# StepDrv.net
KiCad netlist of a schematic drawn in EAGLE
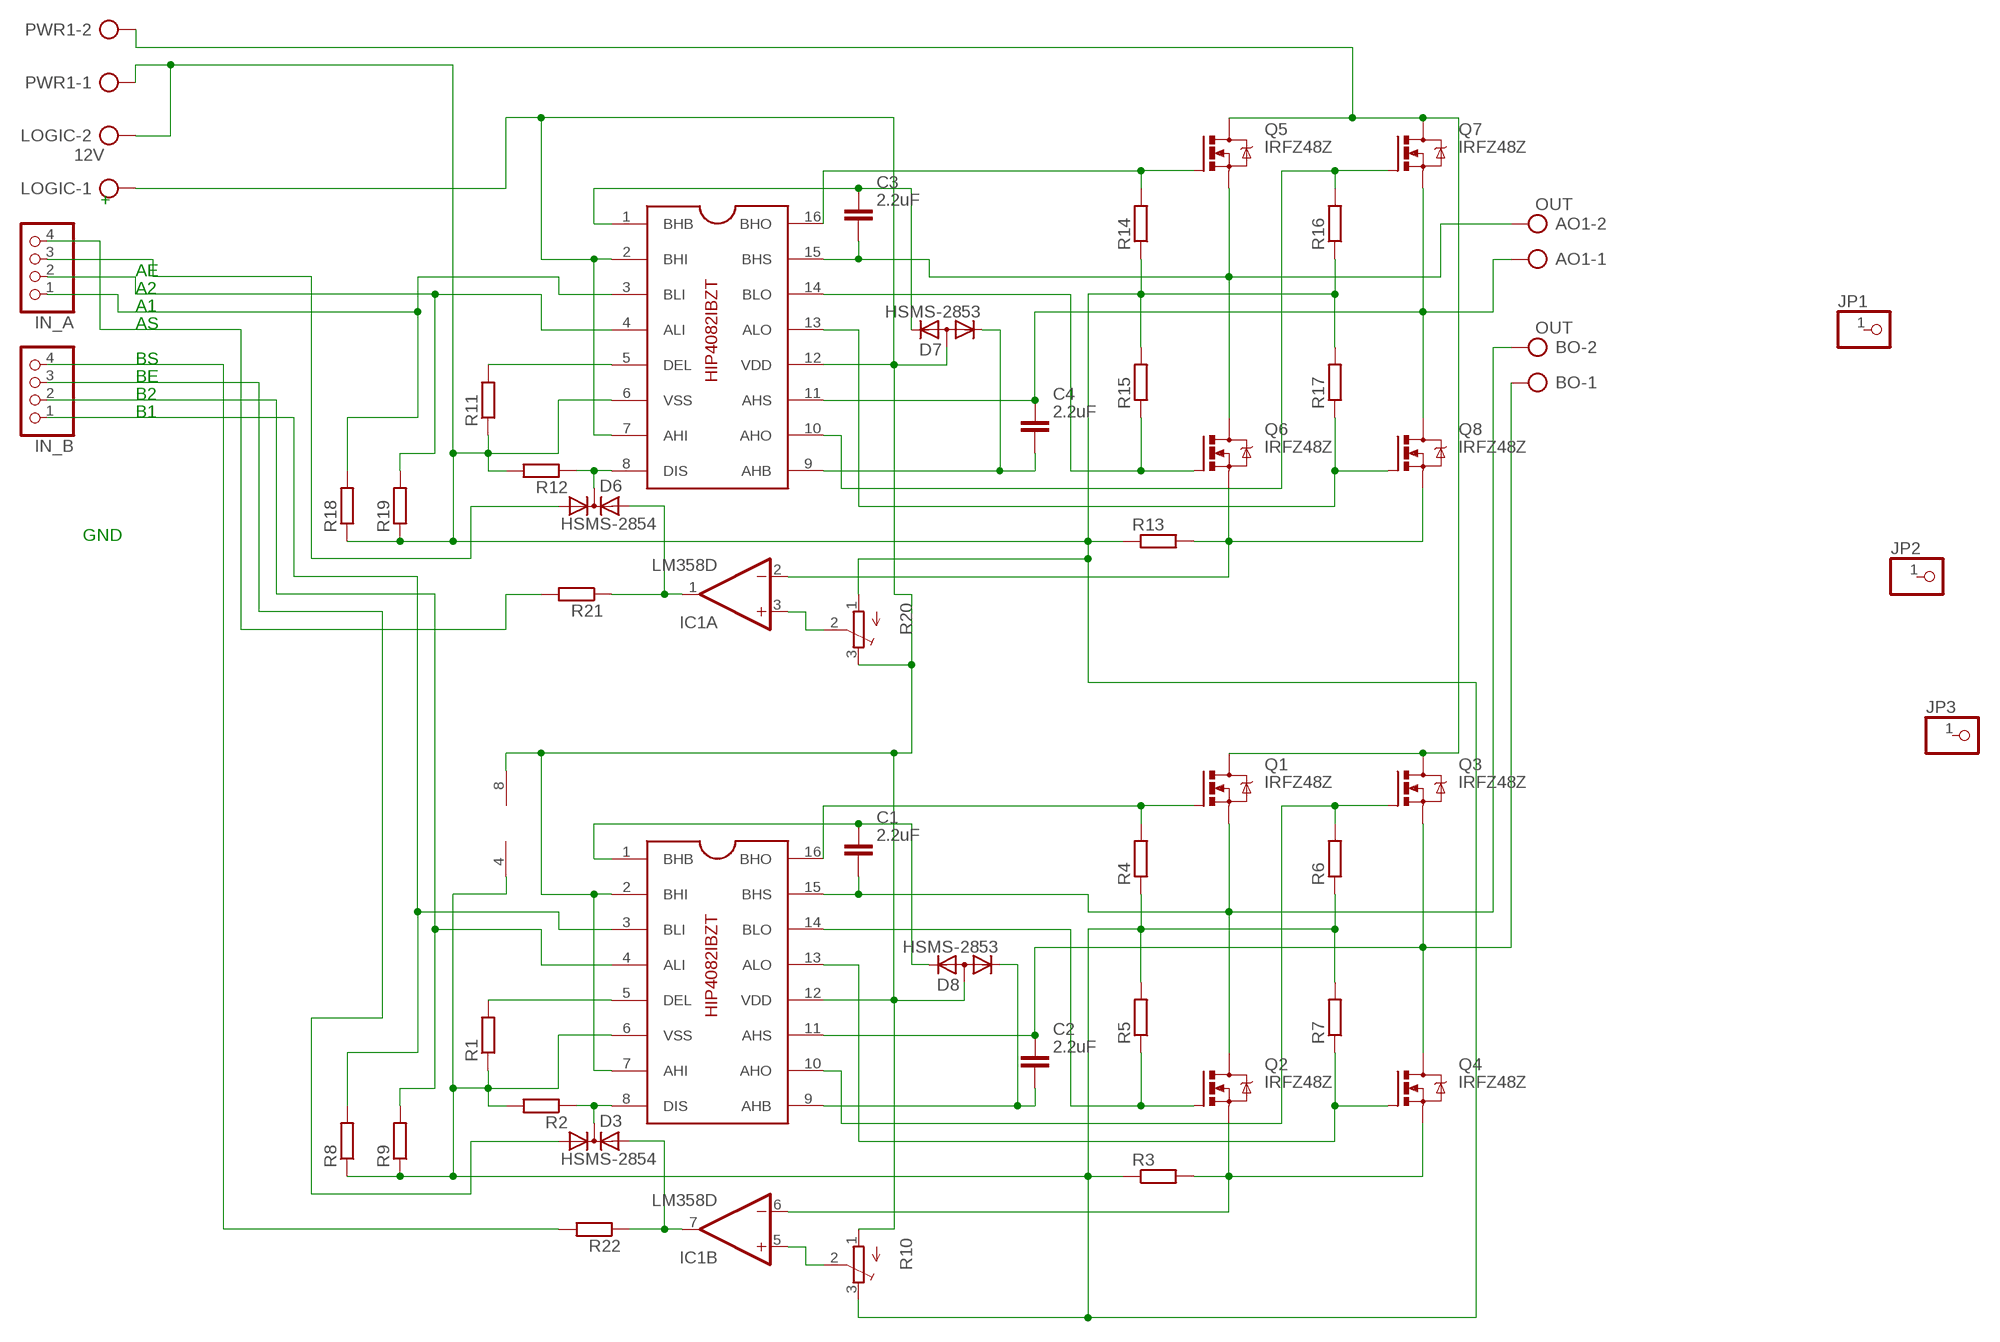
[diagram p0: schematic, sheet 1]

(export (version "E")
  (design (tool "Eeschema 10.0.6"))
  (components
    (comp (ref "AO1")
      (value "OUT")
      (footprint "eagle-import:AK300_2")
      (libsource (lib "eagle-import") (part "AK300/2"))
    )
    (comp (ref "BO")
      (value "OUT")
      (footprint "eagle-import:AK300_2")
      (libsource (lib "eagle-import") (part "AK300/2"))
    )
    (comp (ref "C1")
      (value "2.2uF")
      (footprint "eagle-import:C1206")
      (libsource (lib "eagle-import") (part "CAPACITOR_NPOL-1206"))
    )
    (comp (ref "C2")
      (value "2.2uF")
      (footprint "eagle-import:C1206")
      (libsource (lib "eagle-import") (part "CAPACITOR_NPOL-1206"))
    )
    (comp (ref "C3")
      (value "2.2uF")
      (footprint "eagle-import:C1206")
      (libsource (lib "eagle-import") (part "CAPACITOR_NPOL-1206"))
    )
    (comp (ref "C4")
      (value "2.2uF")
      (footprint "eagle-import:C1206")
      (libsource (lib "eagle-import") (part "CAPACITOR_NPOL-1206"))
    )
    (comp (ref "D3")
      (value "HSMS-2854")
      (footprint "eagle-import:SOT23")
      (libsource (lib "eagle-import") (part "HSMS-2854"))
    )
    (comp (ref "D6")
      (value "HSMS-2854")
      (footprint "eagle-import:SOT23")
      (libsource (lib "eagle-import") (part "HSMS-2854"))
    )
    (comp (ref "D7")
      (value "HSMS-2853")
      (footprint "eagle-import:SOT23")
      (libsource (lib "eagle-import") (part "HSMS-2853"))
    )
    (comp (ref "D8")
      (value "HSMS-2853")
      (footprint "eagle-import:SOT23")
      (libsource (lib "eagle-import") (part "HSMS-2853"))
    )
    (comp (ref "IC1")
      (value "LM358D")
      (footprint "eagle-import:SO08")
      (libsource (lib "eagle-import") (part "LM358D"))
    )
    (comp (ref "IN_A")
      (value "PINHD-1X4")
      (footprint "eagle-import:1X04")
      (libsource (lib "eagle-import") (part "PINHD-1X4"))
    )
    (comp (ref "IN_B")
      (value "PINHD-1X4")
      (footprint "eagle-import:1X04")
      (libsource (lib "eagle-import") (part "PINHD-1X4"))
    )
    (comp (ref "JP1")
      (value "PINHD-1X1")
      (footprint "eagle-import:1X01")
      (libsource (lib "eagle-import") (part "PINHD-1X1"))
    )
    (comp (ref "JP2")
      (value "PINHD-1X1")
      (footprint "eagle-import:1X01")
      (libsource (lib "eagle-import") (part "PINHD-1X1"))
    )
    (comp (ref "JP3")
      (value "PINHD-1X1")
      (footprint "eagle-import:1X01")
      (libsource (lib "eagle-import") (part "PINHD-1X1"))
    )
    (comp (ref "LOGIC")
      (value "12V")
      (footprint "eagle-import:AK300_2")
      (libsource (lib "eagle-import") (part "AK300/2"))
    )
    (comp (ref "PWR1")
      (value "AK300/2")
      (footprint "eagle-import:AK300_2")
      (libsource (lib "eagle-import") (part "AK300/2"))
    )
    (comp (ref "Q1")
      (value "IRFZ48Z")
      (footprint "eagle-import:TO220BH")
      (libsource (lib "eagle-import") (part "IRFZ48Z"))
    )
    (comp (ref "Q2")
      (value "IRFZ48Z")
      (footprint "eagle-import:TO220BH")
      (libsource (lib "eagle-import") (part "IRFZ48Z"))
    )
    (comp (ref "Q3")
      (value "IRFZ48Z")
      (footprint "eagle-import:TO220BH")
      (libsource (lib "eagle-import") (part "IRFZ48Z"))
    )
    (comp (ref "Q4")
      (value "IRFZ48Z")
      (footprint "eagle-import:TO220BH")
      (libsource (lib "eagle-import") (part "IRFZ48Z"))
    )
    (comp (ref "Q5")
      (value "IRFZ48Z")
      (footprint "eagle-import:TO220BH")
      (libsource (lib "eagle-import") (part "IRFZ48Z"))
    )
    (comp (ref "Q6")
      (value "IRFZ48Z")
      (footprint "eagle-import:TO220BH")
      (libsource (lib "eagle-import") (part "IRFZ48Z"))
    )
    (comp (ref "Q7")
      (value "IRFZ48Z")
      (footprint "eagle-import:TO220BH")
      (libsource (lib "eagle-import") (part "IRFZ48Z"))
    )
    (comp (ref "Q8")
      (value "IRFZ48Z")
      (footprint "eagle-import:TO220BH")
      (libsource (lib "eagle-import") (part "IRFZ48Z"))
    )
    (comp (ref "R1")
      (value "R-EU_R1206")
      (footprint "eagle-import:R1206")
      (libsource (lib "eagle-import") (part "R-EU_R1206"))
    )
    (comp (ref "R2")
      (value "R-EU_R1206")
      (footprint "eagle-import:R1206")
      (libsource (lib "eagle-import") (part "R-EU_R1206"))
    )
    (comp (ref "R3")
      (value "R-EU_0922/22")
      (footprint "eagle-import:0922_22")
      (libsource (lib "eagle-import") (part "R-EU_0922/22"))
    )
    (comp (ref "R4")
      (value "R-EU_M1206")
      (footprint "eagle-import:M1206")
      (libsource (lib "eagle-import") (part "R-EU_M1206"))
    )
    (comp (ref "R5")
      (value "R-EU_M1206")
      (footprint "eagle-import:M1206")
      (libsource (lib "eagle-import") (part "R-EU_M1206"))
    )
    (comp (ref "R6")
      (value "R-EU_M1206")
      (footprint "eagle-import:M1206")
      (libsource (lib "eagle-import") (part "R-EU_M1206"))
    )
    (comp (ref "R7")
      (value "R-EU_M1206")
      (footprint "eagle-import:M1206")
      (libsource (lib "eagle-import") (part "R-EU_M1206"))
    )
    (comp (ref "R8")
      (value "R-EU_M1206")
      (footprint "eagle-import:M1206")
      (libsource (lib "eagle-import") (part "R-EU_M1206"))
    )
    (comp (ref "R9")
      (value "R-EU_M1206")
      (footprint "eagle-import:M1206")
      (libsource (lib "eagle-import") (part "R-EU_M1206"))
    )
    (comp (ref "R10")
      (value "TRIM_EU-3223G")
      (footprint "eagle-import:3223G")
      (libsource (lib "eagle-import") (part "TRIM_EU-3223G"))
    )
    (comp (ref "R11")
      (value "R-EU_R1206")
      (footprint "eagle-import:R1206")
      (libsource (lib "eagle-import") (part "R-EU_R1206"))
    )
    (comp (ref "R12")
      (value "R-EU_R1206")
      (footprint "eagle-import:R1206")
      (libsource (lib "eagle-import") (part "R-EU_R1206"))
    )
    (comp (ref "R13")
      (value "R-EU_0922/22")
      (footprint "eagle-import:0922_22")
      (libsource (lib "eagle-import") (part "R-EU_0922/22"))
    )
    (comp (ref "R14")
      (value "R-EU_M1206")
      (footprint "eagle-import:M1206")
      (libsource (lib "eagle-import") (part "R-EU_M1206"))
    )
    (comp (ref "R15")
      (value "R-EU_M1206")
      (footprint "eagle-import:M1206")
      (libsource (lib "eagle-import") (part "R-EU_M1206"))
    )
    (comp (ref "R16")
      (value "R-EU_M1206")
      (footprint "eagle-import:M1206")
      (libsource (lib "eagle-import") (part "R-EU_M1206"))
    )
    (comp (ref "R17")
      (value "R-EU_M1206")
      (footprint "eagle-import:M1206")
      (libsource (lib "eagle-import") (part "R-EU_M1206"))
    )
    (comp (ref "R18")
      (value "R-EU_M1206")
      (footprint "eagle-import:M1206")
      (libsource (lib "eagle-import") (part "R-EU_M1206"))
    )
    (comp (ref "R19")
      (value "R-EU_M1206")
      (footprint "eagle-import:M1206")
      (libsource (lib "eagle-import") (part "R-EU_M1206"))
    )
    (comp (ref "R20")
      (value "TRIM_EU-3223G")
      (footprint "eagle-import:3223G")
      (libsource (lib "eagle-import") (part "TRIM_EU-3223G"))
    )
    (comp (ref "R21")
      (value "R-EU_M1206")
      (footprint "eagle-import:M1206")
      (libsource (lib "eagle-import") (part "R-EU_M1206"))
    )
    (comp (ref "R22")
      (value "R-EU_M1206")
      (footprint "eagle-import:M1206")
      (libsource (lib "eagle-import") (part "R-EU_M1206"))
    )
    (comp (ref "U$1")
      (value "HIP4082IBZT")
      (footprint "eagle-import:SO16")
      (libsource (lib "eagle-import") (part "HIP4082IBZT"))
    )
    (comp (ref "U$2")
      (value "HIP4082IBZT")
      (footprint "eagle-import:SO16")
      (libsource (lib "eagle-import") (part "HIP4082IBZT"))
    )
  )
  (nets
    (net (code "1") (name "Net-(AO1A-KL)") (class "Default")
      (node (ref "AO1") (pin "1") (pinfunction "KL_1") (pintype "passive"))
      (node (ref "C4") (pin "1") (pinfunction "1_1") (pintype "passive"))
      (node (ref "Q7") (pin "S") (pinfunction "S_S") (pintype "passive"))
      (node (ref "Q8") (pin "D") (pinfunction "D_D") (pintype "passive"))
      (node (ref "U$2") (pin "11") (pinfunction "AHS_11") (pintype "output"))
    )
    (net (code "2") (name "Net-(AO1B-KL)") (class "Default")
      (node (ref "AO1") (pin "2") (pinfunction "KL_2") (pintype "passive"))
      (node (ref "C3") (pin "2") (pinfunction "2_2") (pintype "passive"))
      (node (ref "Q5") (pin "S") (pinfunction "S_S") (pintype "passive"))
      (node (ref "Q6") (pin "D") (pinfunction "D_D") (pintype "passive"))
      (node (ref "U$2") (pin "15") (pinfunction "BHS_15") (pintype "output"))
    )
    (net (code "3") (name "Net-(BOA-KL)") (class "Default")
      (node (ref "BO") (pin "1") (pinfunction "KL_1") (pintype "passive"))
      (node (ref "C2") (pin "1") (pinfunction "1_1") (pintype "passive"))
      (node (ref "Q3") (pin "S") (pinfunction "S_S") (pintype "passive"))
      (node (ref "Q4") (pin "D") (pinfunction "D_D") (pintype "passive"))
      (node (ref "U$1") (pin "11") (pinfunction "AHS_11") (pintype "output"))
    )
    (net (code "4") (name "Net-(BOB-KL)") (class "Default")
      (node (ref "BO") (pin "2") (pinfunction "KL_2") (pintype "passive"))
      (node (ref "C1") (pin "2") (pinfunction "2_2") (pintype "passive"))
      (node (ref "Q1") (pin "S") (pinfunction "S_S") (pintype "passive"))
      (node (ref "Q2") (pin "D") (pinfunction "D_D") (pintype "passive"))
      (node (ref "U$1") (pin "15") (pinfunction "BHS_15") (pintype "output"))
    )
    (net (code "5") (name "Net-(D3-A1)") (class "Default")
      (node (ref "D3") (pin "1") (pinfunction "A1_1") (pintype "passive"))
      (node (ref "IN_B") (pin "3") (pinfunction "3_3") (pintype "passive"))
    )
    (net (code "6") (name "Net-(D3-A2)") (class "Default")
      (node (ref "D3") (pin "2") (pinfunction "A2_2") (pintype "passive"))
      (node (ref "IC1") (pin "7") (pinfunction "OUT_7") (pintype "output"))
      (node (ref "R22") (pin "1") (pinfunction "1_1") (pintype "passive"))
    )
    (net (code "7") (name "Net-(D3-C)") (class "Default")
      (node (ref "D3") (pin "3") (pinfunction "C_3") (pintype "passive"))
      (node (ref "R2") (pin "1") (pinfunction "1_1") (pintype "passive"))
      (node (ref "U$1") (pin "8") (pinfunction "DIS_8") (pintype "input"))
    )
    (net (code "8") (name "Net-(D6-A1)") (class "Default")
      (node (ref "D6") (pin "1") (pinfunction "A1_1") (pintype "passive"))
      (node (ref "IN_A") (pin "3") (pinfunction "3_3") (pintype "passive"))
    )
    (net (code "9") (name "Net-(D6-A2)") (class "Default")
      (node (ref "D6") (pin "2") (pinfunction "A2_2") (pintype "passive"))
      (node (ref "IC1") (pin "1") (pinfunction "OUT_1") (pintype "output"))
      (node (ref "R21") (pin "1") (pinfunction "1_1") (pintype "passive"))
    )
    (net (code "10") (name "Net-(D6-C)") (class "Default")
      (node (ref "D6") (pin "3") (pinfunction "C_3") (pintype "passive"))
      (node (ref "R12") (pin "1") (pinfunction "1_1") (pintype "passive"))
      (node (ref "U$2") (pin "8") (pinfunction "DIS_8") (pintype "input"))
    )
    (net (code "11") (name "Net-(D7-A)") (class "Default")
      (node (ref "D7") (pin "3") (pinfunction "A_3") (pintype "passive"))
      (node (ref "D8") (pin "3") (pinfunction "A_3") (pintype "passive"))
      (node (ref "IC1") (pin "8") (pinfunction "V+_8") (pintype "power_in"))
      (node (ref "LOGIC") (pin "1") (pinfunction "KL_1") (pintype "passive"))
      (node (ref "R10") (pin "1") (pinfunction "A_1") (pintype "passive"))
      (node (ref "R20") (pin "3") (pinfunction "E_3") (pintype "passive"))
      (node (ref "U$1") (pin "12") (pinfunction "VDD_12") (pintype "power_in"))
      (node (ref "U$1") (pin "2") (pinfunction "BHI_2") (pintype "input"))
      (node (ref "U$1") (pin "7") (pinfunction "AHI_7") (pintype "input"))
      (node (ref "U$2") (pin "12") (pinfunction "VDD_12") (pintype "power_in"))
      (node (ref "U$2") (pin "2") (pinfunction "BHI_2") (pintype "input"))
      (node (ref "U$2") (pin "7") (pinfunction "AHI_7") (pintype "input"))
    )
    (net (code "12") (name "Net-(D7-K1)") (class "Default")
      (node (ref "C4") (pin "2") (pinfunction "2_2") (pintype "passive"))
      (node (ref "D7") (pin "1") (pinfunction "K1_1") (pintype "passive"))
      (node (ref "U$2") (pin "9") (pinfunction "AHB_9") (pintype "output"))
    )
    (net (code "13") (name "Net-(D7-K2)") (class "Default")
      (node (ref "C3") (pin "1") (pinfunction "1_1") (pintype "passive"))
      (node (ref "D7") (pin "2") (pinfunction "K2_2") (pintype "passive"))
      (node (ref "U$2") (pin "1") (pinfunction "BHB_1") (pintype "input"))
    )
    (net (code "14") (name "Net-(D8-K1)") (class "Default")
      (node (ref "C2") (pin "2") (pinfunction "2_2") (pintype "passive"))
      (node (ref "D8") (pin "1") (pinfunction "K1_1") (pintype "passive"))
      (node (ref "U$1") (pin "9") (pinfunction "AHB_9") (pintype "output"))
    )
    (net (code "15") (name "Net-(D8-K2)") (class "Default")
      (node (ref "C1") (pin "1") (pinfunction "1_1") (pintype "passive"))
      (node (ref "D8") (pin "2") (pinfunction "K2_2") (pintype "passive"))
      (node (ref "U$1") (pin "1") (pinfunction "BHB_1") (pintype "input"))
    )
    (net (code "16") (name "Net-(IC1A-+IN)") (class "Default")
      (node (ref "IC1") (pin "3") (pinfunction "+IN_3") (pintype "input"))
      (node (ref "R20") (pin "2") (pinfunction "S_2") (pintype "passive"))
    )
    (net (code "17") (name "Net-(IC1A--IN)") (class "Default")
      (node (ref "IC1") (pin "2") (pinfunction "-IN_2") (pintype "input"))
      (node (ref "Q6") (pin "S") (pinfunction "S_S") (pintype "passive"))
      (node (ref "Q8") (pin "S") (pinfunction "S_S") (pintype "passive"))
      (node (ref "R13") (pin "2") (pinfunction "2_2") (pintype "passive"))
    )
    (net (code "18") (name "Net-(IC1B-+IN)") (class "Default")
      (node (ref "IC1") (pin "5") (pinfunction "+IN_5") (pintype "input"))
      (node (ref "R10") (pin "2") (pinfunction "S_2") (pintype "passive"))
    )
    (net (code "19") (name "Net-(IC1B--IN)") (class "Default")
      (node (ref "IC1") (pin "6") (pinfunction "-IN_6") (pintype "input"))
      (node (ref "Q2") (pin "S") (pinfunction "S_S") (pintype "passive"))
      (node (ref "Q4") (pin "S") (pinfunction "S_S") (pintype "passive"))
      (node (ref "R3") (pin "2") (pinfunction "2_2") (pintype "passive"))
    )
    (net (code "20") (name "Net-(IC1C-V-)") (class "Default")
      (node (ref "IC1") (pin "4") (pinfunction "V-_4") (pintype "power_in"))
      (node (ref "LOGIC") (pin "2") (pinfunction "KL_2") (pintype "passive"))
      (node (ref "PWR1") (pin "1") (pinfunction "KL_1") (pintype "passive"))
      (node (ref "R1") (pin "1") (pinfunction "1_1") (pintype "passive"))
      (node (ref "R10") (pin "3") (pinfunction "E_3") (pintype "passive"))
      (node (ref "R11") (pin "1") (pinfunction "1_1") (pintype "passive"))
      (node (ref "R12") (pin "2") (pinfunction "2_2") (pintype "passive"))
      (node (ref "R13") (pin "1") (pinfunction "1_1") (pintype "passive"))
      (node (ref "R14") (pin "1") (pinfunction "1_1") (pintype "passive"))
      (node (ref "R15") (pin "2") (pinfunction "2_2") (pintype "passive"))
      (node (ref "R16") (pin "1") (pinfunction "1_1") (pintype "passive"))
      (node (ref "R17") (pin "2") (pinfunction "2_2") (pintype "passive"))
      (node (ref "R18") (pin "1") (pinfunction "1_1") (pintype "passive"))
      (node (ref "R19") (pin "1") (pinfunction "1_1") (pintype "passive"))
      (node (ref "R2") (pin "2") (pinfunction "2_2") (pintype "passive"))
      (node (ref "R20") (pin "1") (pinfunction "A_1") (pintype "passive"))
      (node (ref "R3") (pin "1") (pinfunction "1_1") (pintype "passive"))
      (node (ref "R4") (pin "1") (pinfunction "1_1") (pintype "passive"))
      (node (ref "R5") (pin "2") (pinfunction "2_2") (pintype "passive"))
      (node (ref "R6") (pin "1") (pinfunction "1_1") (pintype "passive"))
      (node (ref "R7") (pin "2") (pinfunction "2_2") (pintype "passive"))
      (node (ref "R8") (pin "1") (pinfunction "1_1") (pintype "passive"))
      (node (ref "R9") (pin "1") (pinfunction "1_1") (pintype "passive"))
      (node (ref "U$1") (pin "6") (pinfunction "VSS_6") (pintype "power_in"))
      (node (ref "U$2") (pin "6") (pinfunction "VSS_6") (pintype "power_in"))
    )
    (net (code "21") (name "Net-(IN_A-Pad4)") (class "Default")
      (node (ref "IN_A") (pin "4") (pinfunction "4_4") (pintype "passive"))
      (node (ref "R21") (pin "2") (pinfunction "2_2") (pintype "passive"))
    )
    (net (code "22") (name "Net-(IN_B-Pad4)") (class "Default")
      (node (ref "IN_B") (pin "4") (pinfunction "4_4") (pintype "passive"))
      (node (ref "R22") (pin "2") (pinfunction "2_2") (pintype "passive"))
    )
    (net (code "23") (name "Net-(PWR1B-KL)") (class "Default")
      (node (ref "PWR1") (pin "2") (pinfunction "KL_2") (pintype "passive"))
      (node (ref "Q1") (pin "D") (pinfunction "D_D") (pintype "passive"))
      (node (ref "Q3") (pin "D") (pinfunction "D_D") (pintype "passive"))
      (node (ref "Q5") (pin "D") (pinfunction "D_D") (pintype "passive"))
      (node (ref "Q7") (pin "D") (pinfunction "D_D") (pintype "passive"))
    )
    (net (code "24") (name "Net-(U$1-AHO)") (class "Default")
      (node (ref "Q3") (pin "G") (pinfunction "G_G") (pintype "passive"))
      (node (ref "R6") (pin "2") (pinfunction "2_2") (pintype "passive"))
      (node (ref "U$1") (pin "10") (pinfunction "AHO_10") (pintype "output"))
    )
    (net (code "25") (name "Net-(U$1-ALI)") (class "Default")
      (node (ref "IN_B") (pin "2") (pinfunction "2_2") (pintype "passive"))
      (node (ref "R9") (pin "2") (pinfunction "2_2") (pintype "passive"))
      (node (ref "U$1") (pin "4") (pinfunction "ALI_4") (pintype "input"))
    )
    (net (code "26") (name "Net-(U$1-ALO)") (class "Default")
      (node (ref "Q4") (pin "G") (pinfunction "G_G") (pintype "passive"))
      (node (ref "R7") (pin "1") (pinfunction "1_1") (pintype "passive"))
      (node (ref "U$1") (pin "13") (pinfunction "ALO_13") (pintype "output"))
    )
    (net (code "27") (name "Net-(U$1-BHO)") (class "Default")
      (node (ref "Q1") (pin "G") (pinfunction "G_G") (pintype "passive"))
      (node (ref "R4") (pin "2") (pinfunction "2_2") (pintype "passive"))
      (node (ref "U$1") (pin "16") (pinfunction "BHO_16") (pintype "output"))
    )
    (net (code "28") (name "Net-(U$1-BLI)") (class "Default")
      (node (ref "IN_B") (pin "1") (pinfunction "1_1") (pintype "passive"))
      (node (ref "R8") (pin "2") (pinfunction "2_2") (pintype "passive"))
      (node (ref "U$1") (pin "3") (pinfunction "BLI_3") (pintype "input"))
    )
    (net (code "29") (name "Net-(U$1-BLO)") (class "Default")
      (node (ref "Q2") (pin "G") (pinfunction "G_G") (pintype "passive"))
      (node (ref "R5") (pin "1") (pinfunction "1_1") (pintype "passive"))
      (node (ref "U$1") (pin "14") (pinfunction "BLO_14") (pintype "output"))
    )
    (net (code "30") (name "Net-(U$1-DEL)") (class "Default")
      (node (ref "R1") (pin "2") (pinfunction "2_2") (pintype "passive"))
      (node (ref "U$1") (pin "5") (pinfunction "DEL_5") (pintype "input"))
    )
    (net (code "31") (name "Net-(U$2-AHO)") (class "Default")
      (node (ref "Q7") (pin "G") (pinfunction "G_G") (pintype "passive"))
      (node (ref "R16") (pin "2") (pinfunction "2_2") (pintype "passive"))
      (node (ref "U$2") (pin "10") (pinfunction "AHO_10") (pintype "output"))
    )
    (net (code "32") (name "Net-(U$2-ALI)") (class "Default")
      (node (ref "IN_A") (pin "2") (pinfunction "2_2") (pintype "passive"))
      (node (ref "R19") (pin "2") (pinfunction "2_2") (pintype "passive"))
      (node (ref "U$2") (pin "4") (pinfunction "ALI_4") (pintype "input"))
    )
    (net (code "33") (name "Net-(U$2-ALO)") (class "Default")
      (node (ref "Q8") (pin "G") (pinfunction "G_G") (pintype "passive"))
      (node (ref "R17") (pin "1") (pinfunction "1_1") (pintype "passive"))
      (node (ref "U$2") (pin "13") (pinfunction "ALO_13") (pintype "output"))
    )
    (net (code "34") (name "Net-(U$2-BHO)") (class "Default")
      (node (ref "Q5") (pin "G") (pinfunction "G_G") (pintype "passive"))
      (node (ref "R14") (pin "2") (pinfunction "2_2") (pintype "passive"))
      (node (ref "U$2") (pin "16") (pinfunction "BHO_16") (pintype "output"))
    )
    (net (code "35") (name "Net-(U$2-BLI)") (class "Default")
      (node (ref "IN_A") (pin "1") (pinfunction "1_1") (pintype "passive"))
      (node (ref "R18") (pin "2") (pinfunction "2_2") (pintype "passive"))
      (node (ref "U$2") (pin "3") (pinfunction "BLI_3") (pintype "input"))
    )
    (net (code "36") (name "Net-(U$2-BLO)") (class "Default")
      (node (ref "Q6") (pin "G") (pinfunction "G_G") (pintype "passive"))
      (node (ref "R15") (pin "1") (pinfunction "1_1") (pintype "passive"))
      (node (ref "U$2") (pin "14") (pinfunction "BLO_14") (pintype "output"))
    )
    (net (code "37") (name "Net-(U$2-DEL)") (class "Default")
      (node (ref "R11") (pin "2") (pinfunction "2_2") (pintype "passive"))
      (node (ref "U$2") (pin "5") (pinfunction "DEL_5") (pintype "input"))
    )
    (net (code "38") (name "unconnected-(JP1-Pad1)") (class "Default")
      (node (ref "JP1") (pin "1") (pinfunction "1_1") (pintype "passive"))
    )
    (net (code "39") (name "unconnected-(JP2-Pad1)") (class "Default")
      (node (ref "JP2") (pin "1") (pinfunction "1_1") (pintype "passive"))
    )
    (net (code "40") (name "unconnected-(JP3-Pad1)") (class "Default")
      (node (ref "JP3") (pin "1") (pinfunction "1_1") (pintype "passive"))
    )
  )
)
